# RFM69Pi_G1.net
KiCad netlist of a schematic drawn in EAGLE
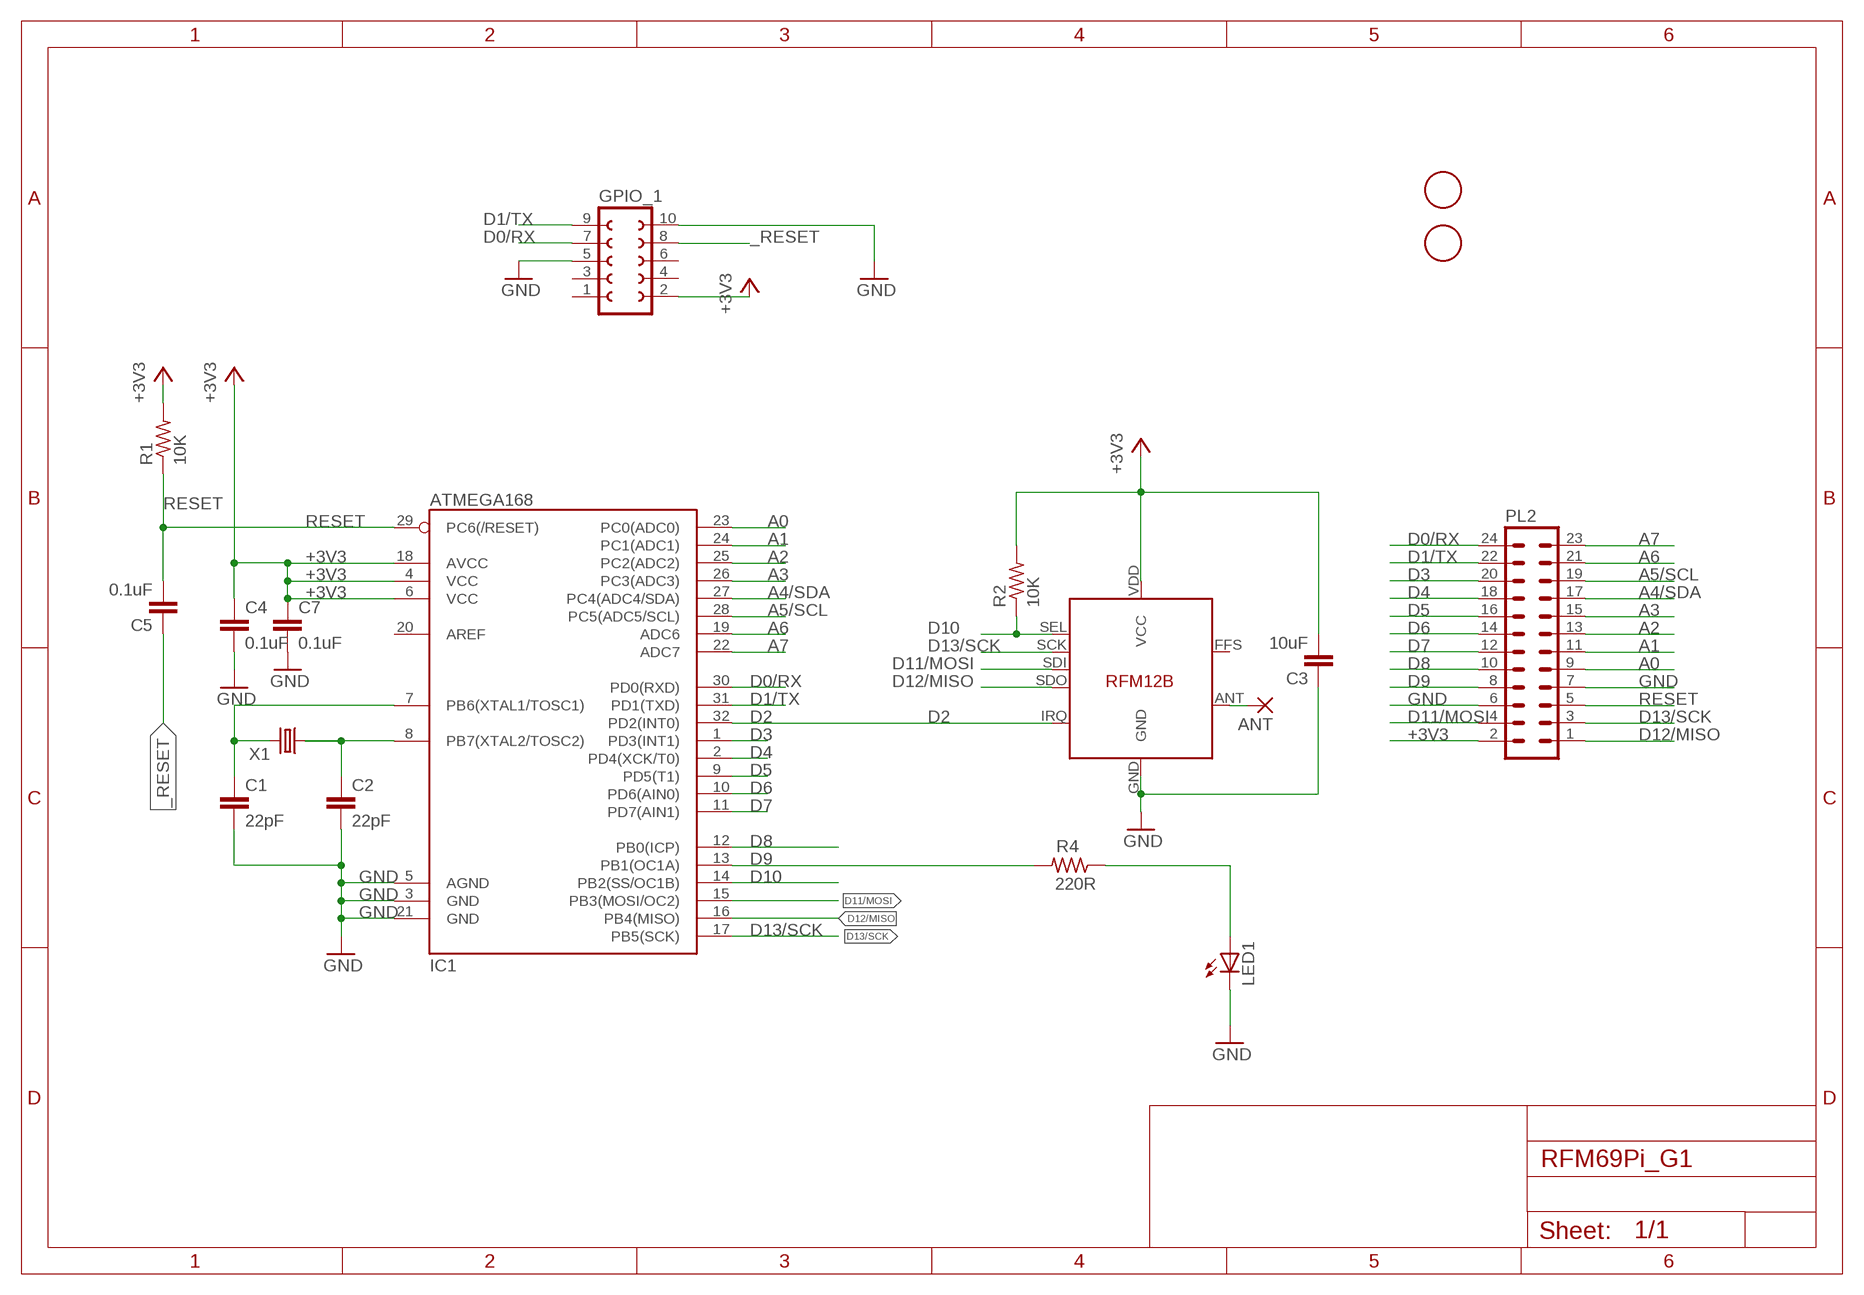
[diagram p0: schematic, sheet 1]

(export (version "E")
  (design (tool "Eeschema 10.0.6"))
  (components
    (comp (ref "ANT")
      (value "1,6/0,8")
      (footprint "eagle-import:1,6_0,8")
      (libsource (lib "eagle-import") (part "1,6/0,8"))
    )
    (comp (ref "C1")
      (value "22pF")
      (footprint "eagle-import:C0603")
      (libsource (lib "eagle-import") (part "C-EUC0603"))
    )
    (comp (ref "C2")
      (value "22pF")
      (footprint "eagle-import:C0603")
      (libsource (lib "eagle-import") (part "C-EUC0603"))
    )
    (comp (ref "C3")
      (value "10uF")
      (footprint "eagle-import:C0603")
      (libsource (lib "eagle-import") (part "C-EUC0603"))
    )
    (comp (ref "C4")
      (value "0.1uF")
      (footprint "eagle-import:C0603")
      (libsource (lib "eagle-import") (part "C-EUC0603"))
    )
    (comp (ref "C5")
      (value "0.1uF")
      (footprint "eagle-import:C0603")
      (libsource (lib "eagle-import") (part "C-EUC0603"))
    )
    (comp (ref "C7")
      (value "0.1uF")
      (footprint "eagle-import:C0603")
      (libsource (lib "eagle-import") (part "resistor_C-EUC0603"))
    )
    (comp (ref "GPIO_1")
      (value "FE05-2")
      (footprint "eagle-import:FE05-2")
      (libsource (lib "eagle-import") (part "FE05-2"))
    )
    (comp (ref "IC1")
      (value "ATMEGA168")
      (footprint "eagle-import:TQFP32-08")
      (libsource (lib "eagle-import") (part "ATMEGA168"))
    )
    (comp (ref "LED1")
      (value "LEDSML0603")
      (footprint "eagle-import:SML0603")
      (libsource (lib "eagle-import") (part "LEDSML0603"))
    )
    (comp (ref "PL2")
      (value "MA12-2")
      (footprint "eagle-import:MA12-2")
      (libsource (lib "eagle-import") (part "MA12-2"))
    )
    (comp (ref "R1")
      (value "10K")
      (footprint "eagle-import:R0603")
      (libsource (lib "eagle-import") (part "R-US_R0603"))
    )
    (comp (ref "R2")
      (value "10K")
      (footprint "eagle-import:R0603")
      (libsource (lib "eagle-import") (part "R-US_R0603"))
    )
    (comp (ref "R4")
      (value "220R")
      (footprint "eagle-import:R0603")
      (libsource (lib "eagle-import") (part "R-US_R0603"))
    )
    (comp (ref "RFM12B-RFM69CW")
      (value "RFM12B")
      (footprint "eagle-import:RFM12B")
      (libsource (lib "eagle-import") (part "RFM12B"))
    )
    (comp (ref "U$1")
      (value "FIDUCIAL")
      (footprint "eagle-import:FIDUCIAL_1MM")
      (libsource (lib "eagle-import") (part "FIDUCIAL"))
    )
    (comp (ref "U$2")
      (value "FIDUCIAL")
      (footprint "eagle-import:FIDUCIAL_1MM")
      (libsource (lib "eagle-import") (part "FIDUCIAL"))
    )
    (comp (ref "X1")
      (value "CRYSTALHC49US")
      (footprint "eagle-import:HC49US")
      (libsource (lib "eagle-import") (part "CRYSTALHC49US"))
    )
  )
  (nets
    (net (code "1") (name "+3V3") (class "Default")
      (node (ref "C3") (pin "2") (pinfunction "2_2") (pintype "passive"))
      (node (ref "C4") (pin "1") (pinfunction "1_1") (pintype "passive"))
      (node (ref "C7") (pin "1") (pinfunction "1_1") (pintype "passive"))
      (node (ref "GPIO_1") (pin "2") (pinfunction "2_2") (pintype "passive"))
      (node (ref "IC1") (pin "18") (pinfunction "AVCC_18") (pintype "bidirectional"))
      (node (ref "IC1") (pin "4") (pinfunction "VCC_4") (pintype "bidirectional"))
      (node (ref "IC1") (pin "6") (pinfunction "VCC_6") (pintype "bidirectional"))
      (node (ref "PL2") (pin "2") (pinfunction "2_2") (pintype "passive"))
      (node (ref "R1") (pin "2") (pinfunction "2_2") (pintype "passive"))
      (node (ref "R2") (pin "2") (pinfunction "2_2") (pintype "passive"))
      (node (ref "RFM12B-RFM69CW") (pin "VDD") (pinfunction "VCC_VDD") (pintype "power_in"))
    )
    (net (code "2") (name "/A0") (class "Default")
      (node (ref "IC1") (pin "23") (pinfunction "PC0(ADC0)_23") (pintype "bidirectional"))
      (node (ref "PL2") (pin "9") (pinfunction "9_9") (pintype "passive"))
    )
    (net (code "3") (name "/A1") (class "Default")
      (node (ref "IC1") (pin "24") (pinfunction "PC1(ADC1)_24") (pintype "bidirectional"))
      (node (ref "PL2") (pin "11") (pinfunction "11_11") (pintype "passive"))
    )
    (net (code "4") (name "/A2") (class "Default")
      (node (ref "IC1") (pin "25") (pinfunction "PC2(ADC2)_25") (pintype "bidirectional"))
      (node (ref "PL2") (pin "13") (pinfunction "13_13") (pintype "passive"))
    )
    (net (code "5") (name "/A3") (class "Default")
      (node (ref "IC1") (pin "26") (pinfunction "PC3(ADC3)_26") (pintype "bidirectional"))
      (node (ref "PL2") (pin "15") (pinfunction "15_15") (pintype "passive"))
    )
    (net (code "6") (name "/A4{slash}SDA") (class "Default")
      (node (ref "IC1") (pin "27") (pinfunction "PC4(ADC4/SDA)_27") (pintype "bidirectional"))
      (node (ref "PL2") (pin "17") (pinfunction "17_17") (pintype "passive"))
    )
    (net (code "7") (name "/A5{slash}SCL") (class "Default")
      (node (ref "IC1") (pin "28") (pinfunction "PC5(ADC5/SCL)_28") (pintype "bidirectional"))
      (node (ref "PL2") (pin "19") (pinfunction "19_19") (pintype "passive"))
    )
    (net (code "8") (name "/A6") (class "Default")
      (node (ref "IC1") (pin "19") (pinfunction "ADC6_19") (pintype "bidirectional"))
      (node (ref "PL2") (pin "21") (pinfunction "21_21") (pintype "passive"))
    )
    (net (code "9") (name "/A7") (class "Default")
      (node (ref "IC1") (pin "22") (pinfunction "ADC7_22") (pintype "bidirectional"))
      (node (ref "PL2") (pin "23") (pinfunction "23_23") (pintype "passive"))
    )
    (net (code "10") (name "/D0{slash}RX") (class "Default")
      (node (ref "GPIO_1") (pin "7") (pinfunction "7_7") (pintype "passive"))
      (node (ref "IC1") (pin "30") (pinfunction "PD0(RXD)_30") (pintype "bidirectional"))
      (node (ref "PL2") (pin "24") (pinfunction "24_24") (pintype "passive"))
    )
    (net (code "11") (name "/D1{slash}TX") (class "Default")
      (node (ref "GPIO_1") (pin "9") (pinfunction "9_9") (pintype "passive"))
      (node (ref "IC1") (pin "31") (pinfunction "PD1(TXD)_31") (pintype "bidirectional"))
      (node (ref "PL2") (pin "22") (pinfunction "22_22") (pintype "passive"))
    )
    (net (code "12") (name "/D2") (class "Default")
      (node (ref "IC1") (pin "32") (pinfunction "PD2(INT0)_32") (pintype "bidirectional"))
      (node (ref "RFM12B-RFM69CW") (pin "IRQ") (pinfunction "IRQ_IRQ") (pintype "open_collector"))
    )
    (net (code "13") (name "/D3") (class "Default")
      (node (ref "IC1") (pin "1") (pinfunction "PD3(INT1)_1") (pintype "bidirectional"))
      (node (ref "PL2") (pin "20") (pinfunction "20_20") (pintype "passive"))
    )
    (net (code "14") (name "/D4") (class "Default")
      (node (ref "IC1") (pin "2") (pinfunction "PD4(XCK/T0)_2") (pintype "bidirectional"))
      (node (ref "PL2") (pin "18") (pinfunction "18_18") (pintype "passive"))
    )
    (net (code "15") (name "/D5") (class "Default")
      (node (ref "IC1") (pin "9") (pinfunction "PD5(T1)_9") (pintype "bidirectional"))
      (node (ref "PL2") (pin "16") (pinfunction "16_16") (pintype "passive"))
    )
    (net (code "16") (name "/D6") (class "Default")
      (node (ref "IC1") (pin "10") (pinfunction "PD6(AIN0)_10") (pintype "bidirectional"))
      (node (ref "PL2") (pin "14") (pinfunction "14_14") (pintype "passive"))
    )
    (net (code "17") (name "/D7") (class "Default")
      (node (ref "IC1") (pin "11") (pinfunction "PD7(AIN1)_11") (pintype "bidirectional"))
      (node (ref "PL2") (pin "12") (pinfunction "12_12") (pintype "passive"))
    )
    (net (code "18") (name "/D8") (class "Default")
      (node (ref "IC1") (pin "12") (pinfunction "PB0(ICP)_12") (pintype "bidirectional"))
      (node (ref "PL2") (pin "10") (pinfunction "10_10") (pintype "passive"))
    )
    (net (code "19") (name "/D9") (class "Default")
      (node (ref "IC1") (pin "13") (pinfunction "PB1(OC1A)_13") (pintype "bidirectional"))
      (node (ref "PL2") (pin "8") (pinfunction "8_8") (pintype "passive"))
      (node (ref "R4") (pin "2") (pinfunction "2_2") (pintype "passive"))
    )
    (net (code "20") (name "/D10") (class "Default")
      (node (ref "IC1") (pin "14") (pinfunction "PB2(SS/OC1B)_14") (pintype "bidirectional"))
      (node (ref "R2") (pin "1") (pinfunction "1_1") (pintype "passive"))
      (node (ref "RFM12B-RFM69CW") (pin "SEL") (pinfunction "SEL_SEL") (pintype "input"))
    )
    (net (code "21") (name "/RESET") (class "Default")
      (node (ref "C5") (pin "2") (pinfunction "2_2") (pintype "passive"))
      (node (ref "IC1") (pin "29") (pinfunction "PC6(/RESET)_29") (pintype "bidirectional"))
      (node (ref "PL2") (pin "5") (pinfunction "5_5") (pintype "passive"))
      (node (ref "R1") (pin "1") (pinfunction "1_1") (pintype "passive"))
    )
    (net (code "22") (name "D11{slash}MOSI") (class "Default")
      (node (ref "IC1") (pin "15") (pinfunction "PB3(MOSI/OC2)_15") (pintype "bidirectional"))
      (node (ref "PL2") (pin "4") (pinfunction "4_4") (pintype "passive"))
      (node (ref "RFM12B-RFM69CW") (pin "SDI") (pinfunction "SDI_SDI") (pintype "input"))
    )
    (net (code "23") (name "D12{slash}MISO") (class "Default")
      (node (ref "IC1") (pin "16") (pinfunction "PB4(MISO)_16") (pintype "bidirectional"))
      (node (ref "PL2") (pin "1") (pinfunction "1_1") (pintype "passive"))
      (node (ref "RFM12B-RFM69CW") (pin "SDO") (pinfunction "SDO_SDO") (pintype "output"))
    )
    (net (code "24") (name "D13{slash}SCK") (class "Default")
      (node (ref "IC1") (pin "17") (pinfunction "PB5(SCK)_17") (pintype "bidirectional"))
      (node (ref "PL2") (pin "3") (pinfunction "3_3") (pintype "passive"))
      (node (ref "RFM12B-RFM69CW") (pin "SCK") (pinfunction "SCK_SCK") (pintype "input"))
    )
    (net (code "25") (name "GND") (class "Default")
      (node (ref "C1") (pin "2") (pinfunction "2_2") (pintype "passive"))
      (node (ref "C2") (pin "2") (pinfunction "2_2") (pintype "passive"))
      (node (ref "C3") (pin "1") (pinfunction "1_1") (pintype "passive"))
      (node (ref "C4") (pin "2") (pinfunction "2_2") (pintype "passive"))
      (node (ref "C7") (pin "2") (pinfunction "2_2") (pintype "passive"))
      (node (ref "GPIO_1") (pin "10") (pinfunction "10_10") (pintype "passive"))
      (node (ref "GPIO_1") (pin "5") (pinfunction "5_5") (pintype "passive"))
      (node (ref "IC1") (pin "21") (pinfunction "GND_21") (pintype "bidirectional"))
      (node (ref "IC1") (pin "3") (pinfunction "GND_3") (pintype "bidirectional"))
      (node (ref "IC1") (pin "5") (pinfunction "AGND_5") (pintype "bidirectional"))
      (node (ref "LED1") (pin "C") (pinfunction "C_C") (pintype "passive"))
      (node (ref "PL2") (pin "6") (pinfunction "6_6") (pintype "passive"))
      (node (ref "PL2") (pin "7") (pinfunction "7_7") (pintype "passive"))
      (node (ref "RFM12B-RFM69CW") (pin "GND") (pinfunction "GND_GND") (pintype "power_in"))
    )
    (net (code "26") (name "Net-(ANT-P)") (class "Default")
      (node (ref "ANT") (pin "1") (pinfunction "P_1") (pintype "passive"))
      (node (ref "RFM12B-RFM69CW") (pin "ANT") (pinfunction "ANT_ANT") (pintype "passive"))
    )
    (net (code "27") (name "Net-(IC1-PB6(XTAL1{slash}TOSC1))") (class "Default")
      (node (ref "C1") (pin "1") (pinfunction "1_1") (pintype "passive"))
      (node (ref "IC1") (pin "7") (pinfunction "PB6(XTAL1/TOSC1)_7") (pintype "bidirectional"))
      (node (ref "X1") (pin "2") (pinfunction "2_2") (pintype "passive"))
    )
    (net (code "28") (name "Net-(IC1-PB7(XTAL2{slash}TOSC2))") (class "Default")
      (node (ref "C2") (pin "1") (pinfunction "1_1") (pintype "passive"))
      (node (ref "IC1") (pin "8") (pinfunction "PB7(XTAL2/TOSC2)_8") (pintype "bidirectional"))
      (node (ref "X1") (pin "1") (pinfunction "1_1") (pintype "passive"))
    )
    (net (code "29") (name "Net-(LED1-PadA)") (class "Default")
      (node (ref "LED1") (pin "A") (pinfunction "A_A") (pintype "passive"))
      (node (ref "R4") (pin "1") (pinfunction "1_1") (pintype "passive"))
    )
    (net (code "30") (name "_RESET") (class "Default")
      (node (ref "C5") (pin "1") (pinfunction "1_1") (pintype "passive"))
      (node (ref "GPIO_1") (pin "8") (pinfunction "8_8") (pintype "passive"))
    )
    (net (code "31") (name "unconnected-(GPIO_1-Pad1)") (class "Default")
      (node (ref "GPIO_1") (pin "1") (pinfunction "1_1") (pintype "passive"))
    )
    (net (code "32") (name "unconnected-(GPIO_1-Pad3)") (class "Default")
      (node (ref "GPIO_1") (pin "3") (pinfunction "3_3") (pintype "passive"))
    )
    (net (code "33") (name "unconnected-(GPIO_1-Pad4)") (class "Default")
      (node (ref "GPIO_1") (pin "4") (pinfunction "4_4") (pintype "passive"))
    )
    (net (code "34") (name "unconnected-(GPIO_1-Pad6)") (class "Default")
      (node (ref "GPIO_1") (pin "6") (pinfunction "6_6") (pintype "passive"))
    )
    (net (code "35") (name "unconnected-(IC1-AREF-Pad20)") (class "Default")
      (node (ref "IC1") (pin "20") (pinfunction "AREF_20") (pintype "bidirectional"))
    )
    (net (code "36") (name "unconnected-(RFM12B-RFM69CW-PadFFS)") (class "Default")
      (node (ref "RFM12B-RFM69CW") (pin "FFS") (pinfunction "FFS_FFS") (pintype "bidirectional"))
    )
  )
)
